# Sheet3_MCU.net
KiCad netlist of a schematic drawn in Altium Designer
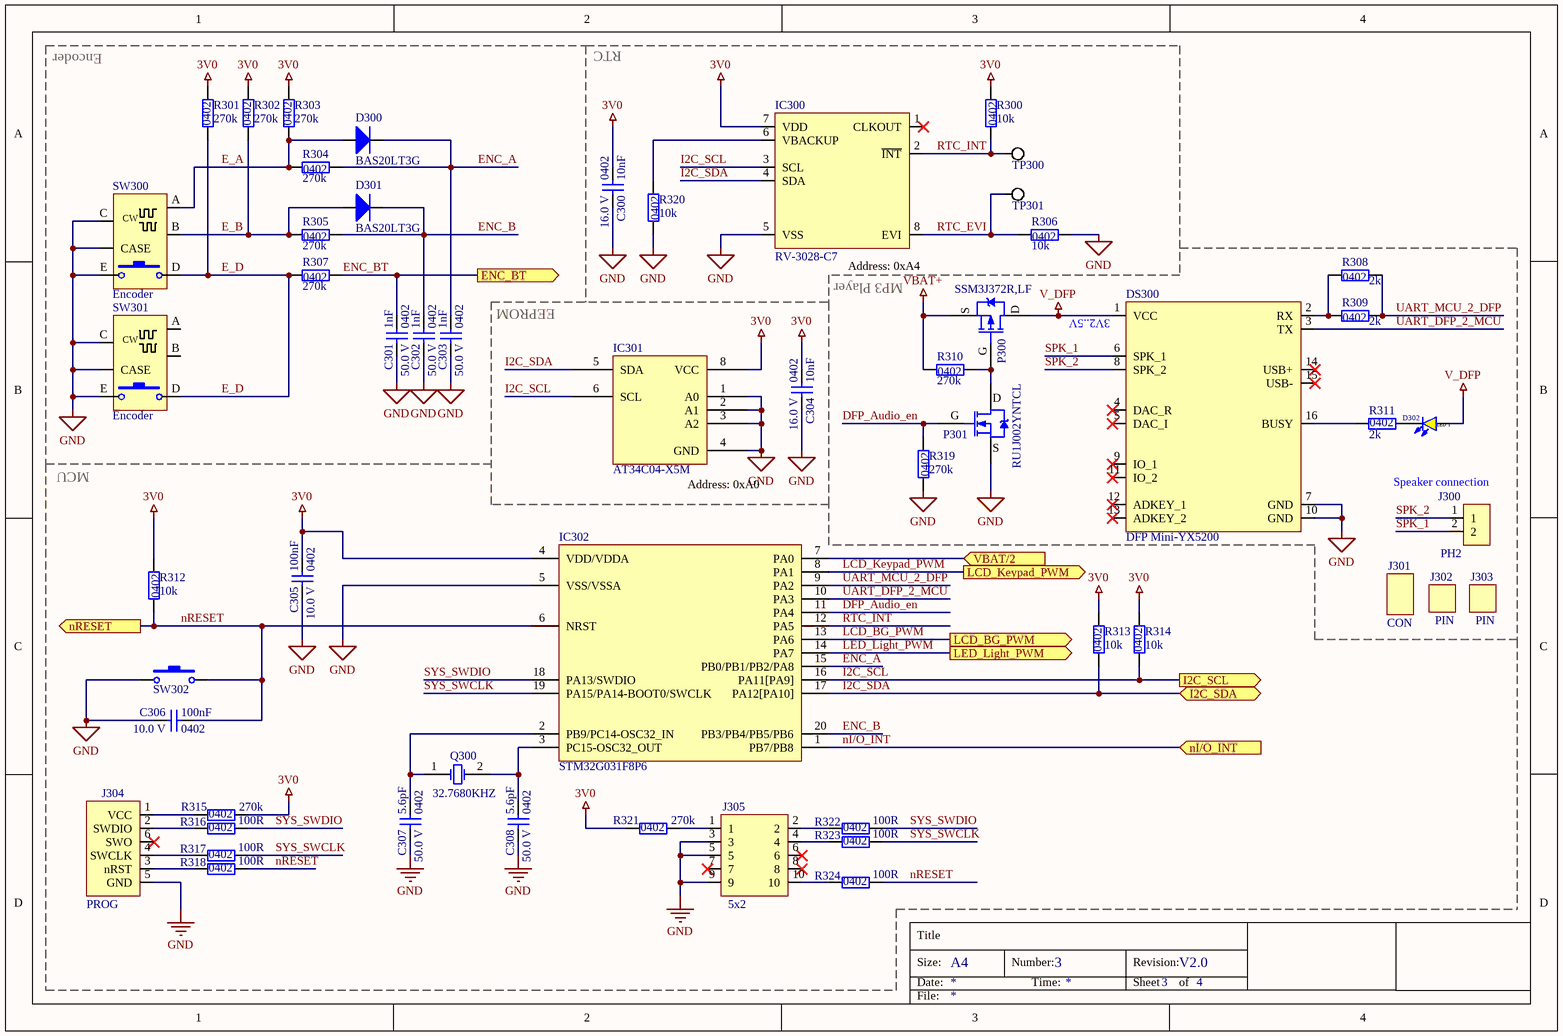
[diagram p0: Sheet3_MCU.SchDoc]

(export (version "E")
  (design (tool "Eeschema 10.0.6"))
  (components
    (comp (ref "C300")
      (value "C 10nF 0402 16V")
      (footprint "0402")
      (description "CAP CER 10000PF 16V Y5V 0402")
      (fields
        (field (name "MANUFACTURER") "Samsung Electro-Mechanics")
        (field (name "MANUFACTURER PART NUMBER") "CL05F103ZO5NNNC")
        (field (name "CAPACITANCE") "10nF")
        (field (name "VOLTAGE") "16.0 V")
      )
      (libsource (lib "CS_Part_Library") (part "CAP_10nF_16V_0402"))
    )
    (comp (ref "C301")
      (value "C 1nF 0402 50V")
      (footprint "0402")
      (description "CAP CER 1000PF 50V C0G/NP0 0402")
      (fields
        (field (name "MANUFACTURER") "Murata Electronics")
        (field (name "MANUFACTURER PART NUMBER") "GRM1555C1H102JA01J")
        (field (name "CAPACITANCE") "1nF")
        (field (name "VOLTAGE") "50.0 V")
      )
      (libsource (lib "CS_Part_Library") (part "CAP_1nF_50V_0402"))
    )
    (comp (ref "C302")
      (value "C 1nF 0402 50V")
      (footprint "0402")
      (description "CAP CER 1000PF 50V C0G/NP0 0402")
      (fields
        (field (name "MANUFACTURER") "Murata Electronics")
        (field (name "MANUFACTURER PART NUMBER") "GRM1555C1H102JA01J")
        (field (name "CAPACITANCE") "1nF")
        (field (name "VOLTAGE") "50.0 V")
      )
      (libsource (lib "CS_Part_Library") (part "CAP_1nF_50V_0402"))
    )
    (comp (ref "C303")
      (value "C 1nF 0402 50V")
      (footprint "0402")
      (description "CAP CER 1000PF 50V C0G/NP0 0402")
      (fields
        (field (name "MANUFACTURER") "Murata Electronics")
        (field (name "MANUFACTURER PART NUMBER") "GRM1555C1H102JA01J")
        (field (name "CAPACITANCE") "1nF")
        (field (name "VOLTAGE") "50.0 V")
      )
      (libsource (lib "CS_Part_Library") (part "CAP_1nF_50V_0402"))
    )
    (comp (ref "C304")
      (value "C 10nF 0402 16V")
      (footprint "0402")
      (description "CAP CER 10000PF 16V Y5V 0402")
      (fields
        (field (name "MANUFACTURER") "Samsung Electro-Mechanics")
        (field (name "MANUFACTURER PART NUMBER") "CL05F103ZO5NNNC")
        (field (name "CAPACITANCE") "10nF")
        (field (name "VOLTAGE") "16.0 V")
      )
      (libsource (lib "CS_Part_Library") (part "CAP_10nF_16V_0402"))
    )
    (comp (ref "C305")
      (value "C 100nF 0402 10V")
      (footprint "0402")
      (description "CAP CER 0.1UF 10V X5R 0402")
      (fields
        (field (name "MANUFACTURER") "Samsung Electro-Mechanics")
        (field (name "MANUFACTURER PART NUMBER") "CL05A104MP5NNNC")
        (field (name "CAPACITANCE") "100nF")
        (field (name "VOLTAGE") "10.0 V")
      )
      (libsource (lib "CS_Part_Library") (part "CAP_100nF_10V_0402"))
    )
    (comp (ref "C306")
      (value "C 100nF 0402 10V")
      (footprint "0402")
      (description "CAP CER 0.1UF 10V X5R 0402")
      (fields
        (field (name "MANUFACTURER") "Samsung Electro-Mechanics")
        (field (name "MANUFACTURER PART NUMBER") "CL05A104MP5NNNC")
        (field (name "CAPACITANCE") "100nF")
        (field (name "VOLTAGE") "10.0 V")
      )
      (libsource (lib "CS_Part_Library") (part "CAP_100nF_10V_0402"))
    )
    (comp (ref "C307")
      (value "C 5.6pF 0402 50V")
      (footprint "0402")
      (description "CAP CER 5.6PF 50V C0G/NP0 0402")
      (fields
        (field (name "MANUFACTURER") "Samsung Electro-Mechanics")
        (field (name "MANUFACTURER PART NUMBER") "CL05C5R6DB5NNNC")
        (field (name "CAPACITANCE") "5.6pF")
        (field (name "VOLTAGE") "50.0 V")
      )
      (libsource (lib "CS_Part_Library") (part "CAP_5.6PF_50V_0402"))
    )
    (comp (ref "C308")
      (value "C 5.6pF 0402 50V")
      (footprint "0402")
      (description "CAP CER 5.6PF 50V C0G/NP0 0402")
      (fields
        (field (name "MANUFACTURER") "Samsung Electro-Mechanics")
        (field (name "MANUFACTURER PART NUMBER") "CL05C5R6DB5NNNC")
        (field (name "CAPACITANCE") "5.6pF")
        (field (name "VOLTAGE") "50.0 V")
      )
      (libsource (lib "CS_Part_Library") (part "CAP_5.6PF_50V_0402"))
    )
    (comp (ref "D300")
      (value "BAS20LT3G")
      (footprint "SOT-23-3")
      (description "DIODE GP 200V 200MA SOT23-3")
      (fields (field (name "MANUFACTURER") "onsemi") (field (name "MANUFACTURER PART NUMBER") "BAS20LT3G"))
      (libsource (lib "Symbols") (part "D_LL_200V_200mA"))
    )
    (comp (ref "D301")
      (value "BAS20LT3G")
      (footprint "SOT-23-3")
      (description "DIODE GP 200V 200MA SOT23-3")
      (fields (field (name "MANUFACTURER") "onsemi") (field (name "MANUFACTURER PART NUMBER") "BAS20LT3G"))
      (libsource (lib "Symbols") (part "D_LL_200V_200mA"))
    )
    (comp (ref "D302")
      (value "LED Y")
      (footprint "LED_0603")
      (description "LED YELLOW DIFFUSED")
      (fields
        (field (name "MANUFACTURER") "Stanley Electric Co")
        (field (name "MANUFACTURER PART NUMBER") "FKY1111C-TR")
      )
      (libsource (lib "CS_Part_Library") (part "D_LED_Yellow_0603"))
    )
    (comp (ref "DS300")
      (value "DFP Mini-YX5200")
      (footprint "DFP_Player_Mini")
      (description "Mini-YX5200 Audio MP3 Modul")
      (fields (field (name "MANUFACTURER") "DFRobot") (field (name "MANUFACTURER PART NUMBER") "DFR0299"))
      (libsource (lib "CS_Part_Library") (part "DFP_Player_mini"))
    )
    (comp (ref "IC300")
      (value "RV-3028-C7")
      (footprint "MC-C7")
      (description "IC RTC CLK/CALENDAR I2C 10SON")
      (fields
        (field (name "MANUFACTURER") "Micro Crystal AG")
        (field (name "MANUFACTURER PART NUMBER") "RV-3028-C7TAQC")
      )
      (libsource (lib "Symbols") (part "IC_RTC_3028-C7"))
    )
    (comp (ref "IC301")
      (value "AT34C04-X5M")
      (footprint "TSSOP-8_4.4mm")
      (description "IC EEPROM 4KBIT I2C 1MHZ 8TSSOP")
      (fields
        (field (name "MANUFACTURER") "Microchip Technology")
        (field (name "MANUFACTURER PART NUMBER") "AT34C04-X5M-T")
      )
      (libsource (lib "CS_Part_Library") (part "IC_EEPROM_AT34C04"))
    )
    (comp (ref "IC302")
      (value "STM32G031F8P6")
      (footprint "TSSOP-20")
      (description "IC MCU 32BIT 32KB FLASH 20TSSOP")
      (fields (field (name "MANUFACTURER") "STMicroelectronics"))
      (libsource (lib "CS_Part_Library") (part "IC_MCU_STM32G031F8P6"))
    )
    (comp (ref "J300")
      (value "PH2")
      (footprint "J_S2B-PH-K-S")
      (description "CONN HEADER R/A 2POS 2MM")
      (fields
        (field (name "MANUFACTURER") "JST Sales America Inc.")
        (field (name "MANUFACTURER PART NUMBER") "S2B-PH-KL(LF)(SN)")
      )
      (libsource (lib "Symbols") (part "J_S2B-PH-KL"))
    )
    (comp (ref "J301")
      (value "CON")
      (description "CONN CONNECTOR PH 2POS 2MM")
      (fields
        (field (name "MANUFACTURER") "JST Sales America Inc.")
        (field (name "MANUFACTURER PART NUMBER") "PHR-2-R")
      )
      (libsource (lib "Symbols") (part "J_PHR-2-R"))
    )
    (comp (ref "J302")
      (value "PIN")
      (description "PIN INSERT")
      (fields
        (field (name "MANUFACTURER") "JST Sales America Inc.")
        (field (name "MANUFACTURER PART NUMBER") "SPH-004T-P0.5S")
      )
      (libsource (lib "Symbols") (part "J_PHR-2-R_PIN"))
    )
    (comp (ref "J303")
      (value "PIN")
      (description "PIN INSERT")
      (fields
        (field (name "MANUFACTURER") "JST Sales America Inc.")
        (field (name "MANUFACTURER PART NUMBER") "SPH-004T-P0.5S")
      )
      (libsource (lib "Symbols") (part "J_PHR-2-R_PIN"))
    )
    (comp (ref "J304")
      (value "PROG")
      (footprint "J_TC2030-IDC-NL")
      (description "SWD Programmer No Legs")
      (fields (field (name "MANUFACTURER") "Tag_connect") (field (name "MANUFACTURER PART NUMBER") "TC2030"))
      (libsource (lib "CS_Part_Library") (part "J_TC2030-IDC-NL"))
    )
    (comp (ref "J305")
      (value "5x2")
      (footprint "J_MH5x2_1.27-STM32")
      (description "CONN HEADER SMD 10POS 1.27MM")
      (fields
        (field (name "MANUFACTURER") "Sullins Connector Solutions")
        (field (name "MANUFACTURER PART NUMBER") "GRPB052VWQS-RC")
      )
      (libsource (lib "Symbols") (part "J_MH5x2_1.27"))
    )
    (comp (ref "P300")
      (value "P PMOS 30V 6A")
      (footprint "SOT-23-3-F")
      (description "MOSFET P-CH 30V 6A SOT23F")
      (fields
        (field (name "MANUFACTURER") "Toshiba Semiconductor and Storage")
        (field (name "MANUFACTURER PART NUMBER") "SSM3J372R,LF")
      )
      (libsource (lib "CS_Part_Library") (part "P_PCH_30V_1W"))
    )
    (comp (ref "P301")
      (value "P_NCH_50V_150mW")
      (footprint "UMT3F")
      (description "MOSFET N-CH 50V 200MA UMT3F")
      (fields
        (field (name "MANUFACTURER") "Rohm Semiconductor")
        (field (name "MANUFACTURER PART NUMBER") "RU1J002YNTCL")
      )
      (libsource (lib "CS_Part_Library") (part "P_NCH_50V_150mW"))
    )
    (comp (ref "Q300")
      (value "32.7680KHZ")
      (footprint "Q2_3.2x1.5")
      (description "CRYSTAL 32.7680KHZ 12.5PF SMD")
      (fields
        (field (name "MANUFACTURER") "NDK America, Inc.")
        (field (name "MANUFACTURER PART NUMBER") "NX3215SA-32.768K-EXS00A-MU00003")
      )
      (libsource (lib "CS_Part_Library") (part "Q_32k768_12p5"))
    )
    (comp (ref "R300")
      (value "R 10k 0402")
      (footprint "0402")
      (description "RES 10K OHM 1% 1/16W 0402")
      (fields
        (field (name "MANUFACTURER") "YAGEO")
        (field (name "MANUFACTURER PART NUMBER") "RC0402FR-0710KL")
        (field (name "RESISTANCE") "10k")
      )
      (libsource (lib "CS_Part_Library") (part "R_10k_0402"))
    )
    (comp (ref "R301")
      (value "R 270k 0402")
      (footprint "0402")
      (description "RES 270K OHM 1% 1/16W 0402")
      (fields
        (field (name "MANUFACTURER") "YAGEO")
        (field (name "MANUFACTURER PART NUMBER") "RC0402FR-07270KL")
        (field (name "RESISTANCE") "270k")
      )
      (libsource (lib "CS_Part_Library") (part "R_270k_0402"))
    )
    (comp (ref "R302")
      (value "R 270k 0402")
      (footprint "0402")
      (description "RES 270K OHM 1% 1/16W 0402")
      (fields
        (field (name "MANUFACTURER") "YAGEO")
        (field (name "MANUFACTURER PART NUMBER") "RC0402FR-07270KL")
        (field (name "RESISTANCE") "270k")
      )
      (libsource (lib "CS_Part_Library") (part "R_270k_0402"))
    )
    (comp (ref "R303")
      (value "R 270k 0402")
      (footprint "0402")
      (description "RES 270K OHM 1% 1/16W 0402")
      (fields
        (field (name "MANUFACTURER") "YAGEO")
        (field (name "MANUFACTURER PART NUMBER") "RC0402FR-07270KL")
        (field (name "RESISTANCE") "270k")
      )
      (libsource (lib "CS_Part_Library") (part "R_270k_0402"))
    )
    (comp (ref "R304")
      (value "R 270k 0402")
      (footprint "0402")
      (description "RES 270K OHM 1% 1/16W 0402")
      (fields
        (field (name "MANUFACTURER") "YAGEO")
        (field (name "MANUFACTURER PART NUMBER") "RC0402FR-07270KL")
        (field (name "RESISTANCE") "270k")
      )
      (libsource (lib "") (part "R_270k_0402_1"))
    )
    (comp (ref "R305")
      (value "R 270k 0402")
      (footprint "0402")
      (description "RES 270K OHM 1% 1/16W 0402")
      (fields
        (field (name "MANUFACTURER") "YAGEO")
        (field (name "MANUFACTURER PART NUMBER") "RC0402FR-07270KL")
        (field (name "RESISTANCE") "270k")
      )
      (libsource (lib "") (part "R_270k_0402_1"))
    )
    (comp (ref "R306")
      (value "R 10k 0402")
      (footprint "0402")
      (description "RES 10K OHM 1% 1/16W 0402")
      (fields
        (field (name "MANUFACTURER") "YAGEO")
        (field (name "MANUFACTURER PART NUMBER") "RC0402FR-0710KL")
        (field (name "RESISTANCE") "10k")
      )
      (libsource (lib "") (part "R_10k_0402_1"))
    )
    (comp (ref "R307")
      (value "R 270k 0402")
      (footprint "0402")
      (description "RES 270K OHM 1% 1/16W 0402")
      (fields
        (field (name "MANUFACTURER") "YAGEO")
        (field (name "MANUFACTURER PART NUMBER") "RC0402FR-07270KL")
        (field (name "RESISTANCE") "270k")
      )
      (libsource (lib "") (part "R_270k_0402_1"))
    )
    (comp (ref "R308")
      (value "R 2k 0402")
      (footprint "0402")
      (description "RES 2K OHM 1% 1/16W 0402")
      (fields
        (field (name "MANUFACTURER") "Stackpole Electronics Inc")
        (field (name "MANUFACTURER PART NUMBER") "RMCF0402FT2K00")
        (field (name "RESISTANCE") "2k")
      )
      (libsource (lib "CS_Part_Library") (part "R_2k_0402"))
    )
    (comp (ref "R309")
      (value "R 2k 0402")
      (footprint "0402")
      (description "RES 2K OHM 1% 1/16W 0402")
      (fields
        (field (name "MANUFACTURER") "Stackpole Electronics Inc")
        (field (name "MANUFACTURER PART NUMBER") "RMCF0402FT2K00")
        (field (name "RESISTANCE") "2k")
      )
      (libsource (lib "CS_Part_Library") (part "R_2k_0402"))
    )
    (comp (ref "R310")
      (value "R 270k 0402")
      (footprint "0402")
      (description "RES 270K OHM 1% 1/16W 0402")
      (fields
        (field (name "MANUFACTURER") "YAGEO")
        (field (name "MANUFACTURER PART NUMBER") "RC0402FR-07270KL")
        (field (name "RESISTANCE") "270k")
      )
      (libsource (lib "") (part "R_270k_0402_1"))
    )
    (comp (ref "R311")
      (value "R 2k 0402")
      (footprint "0402")
      (description "RES 2K OHM 1% 1/16W 0402")
      (fields
        (field (name "MANUFACTURER") "Stackpole Electronics Inc")
        (field (name "MANUFACTURER PART NUMBER") "RMCF0402FT2K00")
        (field (name "RESISTANCE") "2k")
      )
      (libsource (lib "") (part "R_2k_0402_1"))
    )
    (comp (ref "R312")
      (value "R 10k 0402")
      (footprint "0402")
      (description "RES 10K OHM 1% 1/16W 0402")
      (fields
        (field (name "MANUFACTURER") "YAGEO")
        (field (name "MANUFACTURER PART NUMBER") "RC0402FR-0710KL")
        (field (name "RESISTANCE") "10k")
      )
      (libsource (lib "CS_Part_Library") (part "R_10k_0402"))
    )
    (comp (ref "R313")
      (value "R 10k 0402")
      (footprint "0402")
      (description "RES 10K OHM 1% 1/16W 0402")
      (fields
        (field (name "MANUFACTURER") "YAGEO")
        (field (name "MANUFACTURER PART NUMBER") "RC0402FR-0710KL")
        (field (name "RESISTANCE") "10k")
      )
      (libsource (lib "") (part "R_10k_0402_1"))
    )
    (comp (ref "R314")
      (value "R 10k 0402")
      (footprint "0402")
      (description "RES 10K OHM 1% 1/16W 0402")
      (fields
        (field (name "MANUFACTURER") "YAGEO")
        (field (name "MANUFACTURER PART NUMBER") "RC0402FR-0710KL")
        (field (name "RESISTANCE") "10k")
      )
      (libsource (lib "") (part "R_10k_0402_1"))
    )
    (comp (ref "R315")
      (value "R 270k 0402")
      (footprint "0402")
      (description "RES 270K OHM 1% 1/16W 0402")
      (fields
        (field (name "MANUFACTURER") "YAGEO")
        (field (name "MANUFACTURER PART NUMBER") "RC0402FR-07270KL")
        (field (name "RESISTANCE") "270k")
      )
      (libsource (lib "") (part "R_270k_0402_3"))
    )
    (comp (ref "R316")
      (value "R 100R 0402")
      (footprint "0402")
      (description "RES 100 OHM 1% 1/16W 0402")
      (fields
        (field (name "MANUFACTURER") "Stackpole Electronics Inc")
        (field (name "MANUFACTURER PART NUMBER") "RMCF0402FT100R")
        (field (name "RESISTANCE") "100R")
      )
      (libsource (lib "Symbols") (part "R_100R_0402"))
    )
    (comp (ref "R317")
      (value "R 100R 0402")
      (footprint "0402")
      (description "RES 100 OHM 1% 1/16W 0402")
      (fields
        (field (name "MANUFACTURER") "Stackpole Electronics Inc")
        (field (name "MANUFACTURER PART NUMBER") "RMCF0402FT100R")
        (field (name "RESISTANCE") "100R")
      )
      (libsource (lib "Symbols") (part "R_100R_0402"))
    )
    (comp (ref "R318")
      (value "R 100R 0402")
      (footprint "0402")
      (description "RES 100 OHM 1% 1/16W 0402")
      (fields
        (field (name "MANUFACTURER") "Stackpole Electronics Inc")
        (field (name "MANUFACTURER PART NUMBER") "RMCF0402FT100R")
        (field (name "RESISTANCE") "100R")
      )
      (libsource (lib "Symbols") (part "R_100R_0402"))
    )
    (comp (ref "R319")
      (value "R 270k 0402")
      (footprint "0402")
      (description "RES 270K OHM 1% 1/16W 0402")
      (fields
        (field (name "MANUFACTURER") "YAGEO")
        (field (name "MANUFACTURER PART NUMBER") "RC0402FR-07270KL")
        (field (name "RESISTANCE") "270k")
      )
      (libsource (lib "") (part "R_270k_0402_2"))
    )
    (comp (ref "R320")
      (value "R 10k 0402")
      (footprint "0402")
      (description "RES 10K OHM 1% 1/16W 0402")
      (fields
        (field (name "MANUFACTURER") "YAGEO")
        (field (name "MANUFACTURER PART NUMBER") "RC0402FR-0710KL")
        (field (name "RESISTANCE") "10k")
      )
      (libsource (lib "CS_Part_Library") (part "R_10k_0402"))
    )
    (comp (ref "R321")
      (value "R 270k 0402")
      (footprint "0402")
      (description "RES 270K OHM 1% 1/16W 0402")
      (fields
        (field (name "MANUFACTURER") "YAGEO")
        (field (name "MANUFACTURER PART NUMBER") "RC0402FR-07270KL")
        (field (name "RESISTANCE") "270k")
      )
      (libsource (lib "") (part "R_270k_0402_3"))
    )
    (comp (ref "R322")
      (value "R 100R 0402")
      (footprint "0402")
      (description "RES 100 OHM 1% 1/16W 0402")
      (fields
        (field (name "MANUFACTURER") "Stackpole Electronics Inc")
        (field (name "MANUFACTURER PART NUMBER") "RMCF0402FT100R")
        (field (name "RESISTANCE") "100R")
      )
      (libsource (lib "Symbols") (part "R_100R_0402"))
    )
    (comp (ref "R323")
      (value "R 100R 0402")
      (footprint "0402")
      (description "RES 100 OHM 1% 1/16W 0402")
      (fields
        (field (name "MANUFACTURER") "Stackpole Electronics Inc")
        (field (name "MANUFACTURER PART NUMBER") "RMCF0402FT100R")
        (field (name "RESISTANCE") "100R")
      )
      (libsource (lib "Symbols") (part "R_100R_0402"))
    )
    (comp (ref "R324")
      (value "R 100R 0402")
      (footprint "0402")
      (description "RES 100 OHM 1% 1/16W 0402")
      (fields
        (field (name "MANUFACTURER") "Stackpole Electronics Inc")
        (field (name "MANUFACTURER PART NUMBER") "RMCF0402FT100R")
        (field (name "RESISTANCE") "100R")
      )
      (libsource (lib "Symbols") (part "R_100R_0402"))
    )
    (comp (ref "SW300")
      (value "Encoder")
      (footprint "PEC11R")
      (description "ROTARY ENCODER MECHANICAL 12PPR")
      (fields
        (field (name "MANUFACTURER") "Bourns Inc.")
        (field (name "MANUFACTURER PART NUMBER") "PEC11R-4220F-S0012")
      )
      (libsource (lib "CS_Part_Library") (part "ENC_12_THT"))
    )
    (comp (ref "SW301")
      (value "Encoder")
      (footprint "PEC11R")
      (description "ROTARY ENCODER MECHANICAL 12PPR")
      (fields
        (field (name "MANUFACTURER") "Bourns Inc.")
        (field (name "MANUFACTURER PART NUMBER") "PEC11R-4220F-S0012")
      )
      (libsource (lib "CS_Part_Library") (part "ENC_12_THT"))
    )
    (comp (ref "SW302")
      (value "SW")
      (footprint "SW_PTS810")
      (description "SWITCH TACTILE SPST-NO 0.05A 16V")
      (fields
        (field (name "MANUFACTURER") "C&K")
        (field (name "MANUFACTURER PART NUMBER") "PTS810 SJM 250 SMTR LFS")
      )
      (libsource (lib "Symbols") (part "SW_TactileSW_V"))
    )
    (comp (ref "TP300")
      (value "TP")
      (footprint "TP_1mm")
      (description "Test Point 1mm")
      (libsource (lib "CS_Part_Library") (part "TP_1mm"))
    )
    (comp (ref "TP301")
      (value "TP")
      (footprint "TP_1mm")
      (description "Test Point 1mm")
      (libsource (lib "CS_Part_Library") (part "TP_1mm"))
    )
  )
  (nets
    (net (code "1") (name "/DFP_Audio_en") (class "Default")
      (node (ref "IC302") (pin "11") (pinfunction "PA4_11") (pintype "passive"))
      (node (ref "P301") (pin "1") (pinfunction "G_1") (pintype "passive"))
      (node (ref "R319") (pin "1") (pinfunction "1_1") (pintype "passive"))
    )
    (net (code "2") (name "/ENC_A") (class "Default")
      (node (ref "C303") (pin "2") (pinfunction "2_2") (pintype "passive"))
      (node (ref "D300") (pin "3") (pinfunction "K_3") (pintype "passive"))
      (node (ref "IC302") (pin "15") (pinfunction "PB0/PB1/PB2/PA8_15") (pintype "passive"))
      (node (ref "R304") (pin "1") (pinfunction "1_1") (pintype "passive"))
    )
    (net (code "3") (name "/ENC_B") (class "Default")
      (node (ref "C302") (pin "2") (pinfunction "2_2") (pintype "passive"))
      (node (ref "D301") (pin "3") (pinfunction "K_3") (pintype "passive"))
      (node (ref "IC302") (pin "20") (pinfunction "PB3/PB4/PB5/PB6_20") (pintype "passive"))
      (node (ref "R305") (pin "1") (pinfunction "1_1") (pintype "passive"))
    )
    (net (code "4") (name "/ENC_BT") (class "Default")
      (node (ref "C301") (pin "2") (pinfunction "2_2") (pintype "passive"))
      (node (ref "R307") (pin "1") (pinfunction "1_1") (pintype "passive"))
    )
    (net (code "5") (name "/E_A") (class "Default")
      (node (ref "D300") (pin "1") (pinfunction "A_1") (pintype "passive"))
      (node (ref "R303") (pin "1") (pinfunction "1_1") (pintype "passive"))
      (node (ref "R304") (pin "2") (pinfunction "2_2") (pintype "passive"))
      (node (ref "SW300") (pin "A") (pinfunction "A_A") (pintype "passive"))
    )
    (net (code "6") (name "/E_B") (class "Default")
      (node (ref "D301") (pin "1") (pinfunction "A_1") (pintype "passive"))
      (node (ref "R302") (pin "1") (pinfunction "1_1") (pintype "passive"))
      (node (ref "R305") (pin "2") (pinfunction "2_2") (pintype "passive"))
      (node (ref "SW300") (pin "B") (pinfunction "B_B") (pintype "passive"))
    )
    (net (code "7") (name "/E_D") (class "Default")
      (node (ref "R301") (pin "1") (pinfunction "1_1") (pintype "passive"))
      (node (ref "R307") (pin "2") (pinfunction "2_2") (pintype "passive"))
      (node (ref "SW300") (pin "D") (pinfunction "D_D") (pintype "passive"))
      (node (ref "SW301") (pin "D") (pinfunction "D_D") (pintype "passive"))
    )
    (net (code "8") (name "/I2C_SCL") (class "Default")
      (node (ref "IC300") (pin "3") (pinfunction "SCL_3") (pintype "passive"))
      (node (ref "IC301") (pin "6") (pinfunction "SCL_6") (pintype "passive"))
      (node (ref "IC302") (pin "16") (pinfunction "PA11[PA9]_16") (pintype "passive"))
      (node (ref "R314") (pin "1") (pinfunction "1_1") (pintype "passive"))
    )
    (net (code "9") (name "/I2C_SDA") (class "Default")
      (node (ref "IC300") (pin "4") (pinfunction "SDA_4") (pintype "passive"))
      (node (ref "IC301") (pin "5") (pinfunction "SDA_5") (pintype "passive"))
      (node (ref "IC302") (pin "17") (pinfunction "PA12[PA10]_17") (pintype "passive"))
      (node (ref "R313") (pin "1") (pinfunction "1_1") (pintype "passive"))
    )
    (net (code "10") (name "/LCD_BG_PWM") (class "Default")
      (node (ref "IC302") (pin "13") (pinfunction "PA6_13") (pintype "passive"))
    )
    (net (code "11") (name "/LCD_Keypad_PWM") (class "Default")
      (node (ref "IC302") (pin "8") (pinfunction "PA1_8") (pintype "passive"))
    )
    (net (code "12") (name "/LED_Light_PWM") (class "Default")
      (node (ref "IC302") (pin "14") (pinfunction "PA7_14") (pintype "passive"))
    )
    (net (code "13") (name "/RTC_EVI") (class "Default")
      (node (ref "IC300") (pin "8") (pinfunction "EVI_8") (pintype "passive"))
      (node (ref "R306") (pin "1") (pinfunction "1_1") (pintype "passive"))
      (node (ref "TP301") (pin "1") (pinfunction "TP_1") (pintype "passive"))
    )
    (net (code "14") (name "/RTC_INT") (class "Default")
      (node (ref "IC300") (pin "2") (pinfunction "~{INT}_2") (pintype "passive"))
      (node (ref "IC302") (pin "12") (pinfunction "PA5_12") (pintype "passive"))
      (node (ref "R300") (pin "1") (pinfunction "1_1") (pintype "passive"))
      (node (ref "TP300") (pin "1") (pinfunction "TP_1") (pintype "passive"))
    )
    (net (code "15") (name "/SPK_1") (class "Default")
      (node (ref "DS300") (pin "6") (pinfunction "SPK_1_6") (pintype "passive"))
      (node (ref "J300") (pin "2") (pinfunction "2_2") (pintype "passive"))
    )
    (net (code "16") (name "/SPK_2") (class "Default")
      (node (ref "DS300") (pin "8") (pinfunction "SPK_2_8") (pintype "passive"))
      (node (ref "J300") (pin "1") (pinfunction "1_1") (pintype "passive"))
    )
    (net (code "17") (name "/SYS_SWCLK") (class "Default")
      (node (ref "IC302") (pin "19") (pinfunction "PA15/PA14-BOOT0/SWCLK_19") (pintype "passive"))
      (node (ref "R317") (pin "2") (pinfunction "2_2") (pintype "passive"))
      (node (ref "R323") (pin "2") (pinfunction "2_2") (pintype "passive"))
    )
    (net (code "18") (name "/SYS_SWDIO") (class "Default")
      (node (ref "IC302") (pin "18") (pinfunction "PA13/SWDIO_18") (pintype "passive"))
      (node (ref "R316") (pin "2") (pinfunction "2_2") (pintype "passive"))
      (node (ref "R322") (pin "2") (pinfunction "2_2") (pintype "passive"))
    )
    (net (code "19") (name "/UART_DFP_2_MCU") (class "Default")
      (node (ref "DS300") (pin "3") (pinfunction "TX_3") (pintype "passive"))
      (node (ref "IC302") (pin "10") (pinfunction "PA3_10") (pintype "passive"))
    )
    (net (code "20") (name "/UART_MCU_2_DFP") (class "Default")
      (node (ref "IC302") (pin "9") (pinfunction "PA2_9") (pintype "passive"))
      (node (ref "R308") (pin "1") (pinfunction "1_1") (pintype "passive"))
      (node (ref "R309") (pin "1") (pinfunction "1_1") (pintype "passive"))
    )
    (net (code "21") (name "/VBAT{slash}2") (class "Default")
      (node (ref "IC302") (pin "7") (pinfunction "PA0_7") (pintype "passive"))
    )
    (net (code "22") (name "/nI{slash}O_INT") (class "Default")
      (node (ref "IC302") (pin "1") (pinfunction "PB7/PB8_1") (pintype "passive"))
    )
    (net (code "23") (name "/nRESET") (class "Default")
      (node (ref "C306") (pin "2") (pinfunction "2_2") (pintype "passive"))
      (node (ref "IC302") (pin "6") (pinfunction "NRST_6") (pintype "passive"))
      (node (ref "R312") (pin "1") (pinfunction "1_1") (pintype "passive"))
      (node (ref "R318") (pin "2") (pinfunction "2_2") (pintype "passive"))
      (node (ref "R324") (pin "2") (pinfunction "2_2") (pintype "passive"))
      (node (ref "SW302") (pin "3") (pinfunction "2,_3_3") (pintype "passive"))
    )
    (net (code "24") (name "3V0") (class "Default")
      (node (ref "C300") (pin "2") (pinfunction "2_2") (pintype "passive"))
      (node (ref "C304") (pin "2") (pinfunction "2_2") (pintype "passive"))
      (node (ref "C305") (pin "2") (pinfunction "2_2") (pintype "passive"))
      (node (ref "IC300") (pin "7") (pinfunction "VDD_7") (pintype "passive"))
      (node (ref "IC301") (pin "8") (pinfunction "VCC_8") (pintype "passive"))
      (node (ref "IC302") (pin "4") (pinfunction "VDD/VDDA_4") (pintype "passive"))
      (node (ref "R300") (pin "2") (pinfunction "2_2") (pintype "passive"))
      (node (ref "R301") (pin "2") (pinfunction "2_2") (pintype "passive"))
      (node (ref "R302") (pin "2") (pinfunction "2_2") (pintype "passive"))
      (node (ref "R303") (pin "2") (pinfunction "2_2") (pintype "passive"))
      (node (ref "R312") (pin "2") (pinfunction "2_2") (pintype "passive"))
      (node (ref "R313") (pin "2") (pinfunction "2_2") (pintype "passive"))
      (node (ref "R314") (pin "2") (pinfunction "2_2") (pintype "passive"))
      (node (ref "R315") (pin "2") (pinfunction "2_2") (pintype "passive"))
      (node (ref "R321") (pin "1") (pinfunction "1_1") (pintype "passive"))
    )
    (net (code "25") (name "GND") (class "Default")
      (node (ref "C300") (pin "1") (pinfunction "1_1") (pintype "passive"))
      (node (ref "C301") (pin "1") (pinfunction "1_1") (pintype "passive"))
      (node (ref "C302") (pin "1") (pinfunction "1_1") (pintype "passive"))
      (node (ref "C303") (pin "1") (pinfunction "1_1") (pintype "passive"))
      (node (ref "C304") (pin "1") (pinfunction "1_1") (pintype "passive"))
      (node (ref "C305") (pin "1") (pinfunction "1_1") (pintype "passive"))
      (node (ref "C306") (pin "1") (pinfunction "1_1") (pintype "passive"))
      (node (ref "C307") (pin "1") (pinfunction "1_1") (pintype "passive"))
      (node (ref "C308") (pin "1") (pinfunction "1_1") (pintype "passive"))
      (node (ref "DS300") (pin "10") (pinfunction "GND_10") (pintype "passive"))
      (node (ref "DS300") (pin "7") (pinfunction "GND_7") (pintype "passive"))
      (node (ref "IC300") (pin "5") (pinfunction "VSS_5") (pintype "passive"))
      (node (ref "IC301") (pin "1") (pinfunction "A0_1") (pintype "passive"))
      (node (ref "IC301") (pin "2") (pinfunction "A1_2") (pintype "passive"))
      (node (ref "IC301") (pin "3") (pinfunction "A2_3") (pintype "passive"))
      (node (ref "IC301") (pin "4") (pinfunction "GND_4") (pintype "passive"))
      (node (ref "IC302") (pin "5") (pinfunction "VSS/VSSA_5") (pintype "passive"))
      (node (ref "J304") (pin "5") (pinfunction "GND_5") (pintype "passive"))
      (node (ref "J305") (pin "3") (pinfunction "3_3") (pintype "passive"))
      (node (ref "J305") (pin "5") (pinfunction "5_5") (pintype "passive"))
      (node (ref "J305") (pin "9") (pinfunction "9_9") (pintype "passive"))
      (node (ref "P301") (pin "2") (pinfunction "S_2") (pintype "passive"))
      (node (ref "R306") (pin "2") (pinfunction "2_2") (pintype "passive"))
      (node (ref "R319") (pin "2") (pinfunction "2_2") (pintype "passive"))
      (node (ref "R320") (pin "1") (pinfunction "1_1") (pintype "passive"))
      (node (ref "SW300") (pin "C") (pinfunction "C_C") (pintype "passive"))
      (node (ref "SW300") (pin "CASE") (pinfunction "CASE_CASE") (pintype "passive"))
      (node (ref "SW300") (pin "E") (pinfunction "E_E") (pintype "passive"))
      (node (ref "SW301") (pin "C") (pinfunction "C_C") (pintype "passive"))
      (node (ref "SW301") (pin "CASE") (pinfunction "CASE_CASE") (pintype "passive"))
      (node (ref "SW301") (pin "E") (pinfunction "E_E") (pintype "passive"))
      (node (ref "SW302") (pin "1") (pinfunction "1,_2_1") (pintype "passive"))
    )
    (net (code "26") (name "Net-(D302-PadK)") (class "Default")
      (node (ref "D302") (pin "K") (pinfunction "K_K") (pintype "passive"))
      (node (ref "R311") (pin "2") (pinfunction "2_2") (pintype "passive"))
    )
    (net (code "27") (name "Net-(DS300-BUSY)") (class "Default")
      (node (ref "DS300") (pin "16") (pinfunction "BUSY_16") (pintype "passive"))
      (node (ref "R311") (pin "1") (pinfunction "1_1") (pintype "passive"))
    )
    (net (code "28") (name "Net-(DS300-RX)") (class "Default")
      (node (ref "DS300") (pin "2") (pinfunction "RX_2") (pintype "passive"))
      (node (ref "R308") (pin "2") (pinfunction "2_2") (pintype "passive"))
      (node (ref "R309") (pin "2") (pinfunction "2_2") (pintype "passive"))
    )
    (net (code "29") (name "Net-(IC300-VBACKUP)") (class "Default")
      (node (ref "IC300") (pin "6") (pinfunction "VBACKUP_6") (pintype "passive"))
      (node (ref "R320") (pin "2") (pinfunction "2_2") (pintype "passive"))
    )
    (net (code "30") (name "Net-(IC302-PB9{slash}PC14-OSC32_IN)") (class "Default")
      (node (ref "C307") (pin "2") (pinfunction "2_2") (pintype "passive"))
      (node (ref "IC302") (pin "2") (pinfunction "PB9/PC14-OSC32_IN_2") (pintype "passive"))
      (node (ref "Q300") (pin "1") (pinfunction "OSC1_1") (pintype "passive"))
    )
    (net (code "31") (name "Net-(IC302-PC15-OSC32_OUT)") (class "Default")
      (node (ref "C308") (pin "2") (pinfunction "2_2") (pintype "passive"))
      (node (ref "IC302") (pin "3") (pinfunction "PC15-OSC32_OUT_3") (pintype "passive"))
      (node (ref "Q300") (pin "2") (pinfunction "OSC2_2") (pintype "passive"))
    )
    (net (code "32") (name "Net-(J304-SWCLK)") (class "Default")
      (node (ref "J304") (pin "4") (pinfunction "SWCLK_4") (pintype "passive"))
      (node (ref "R317") (pin "1") (pinfunction "1_1") (pintype "passive"))
    )
    (net (code "33") (name "Net-(J304-SWDIO)") (class "Default")
      (node (ref "J304") (pin "2") (pinfunction "SWDIO_2") (pintype "passive"))
      (node (ref "R316") (pin "1") (pinfunction "1_1") (pintype "passive"))
    )
    (net (code "34") (name "Net-(J304-VCC)") (class "Default")
      (node (ref "J304") (pin "1") (pinfunction "VCC_1") (pintype "passive"))
      (node (ref "R315") (pin "1") (pinfunction "1_1") (pintype "passive"))
    )
    (net (code "35") (name "Net-(J304-nRST)") (class "Default")
      (node (ref "J304") (pin "3") (pinfunction "nRST_3") (pintype "passive"))
      (node (ref "R318") (pin "1") (pinfunction "1_1") (pintype "passive"))
    )
    (net (code "36") (name "Net-(J305-Pad1)") (class "Default")
      (node (ref "J305") (pin "1") (pinfunction "1_1") (pintype "passive"))
      (node (ref "R321") (pin "2") (pinfunction "2_2") (pintype "passive"))
    )
    (net (code "37") (name "Net-(J305-Pad2)") (class "Default")
      (node (ref "J305") (pin "2") (pinfunction "2_2") (pintype "passive"))
      (node (ref "R322") (pin "1") (pinfunction "1_1") (pintype "passive"))
    )
    (net (code "38") (name "Net-(J305-Pad4)") (class "Default")
      (node (ref "J305") (pin "4") (pinfunction "4_4") (pintype "passive"))
      (node (ref "R323") (pin "1") (pinfunction "1_1") (pintype "passive"))
    )
    (net (code "39") (name "Net-(J305-Pad10)") (class "Default")
      (node (ref "J305") (pin "10") (pinfunction "10_10") (pintype "passive"))
      (node (ref "R324") (pin "1") (pinfunction "1_1") (pintype "passive"))
    )
    (net (code "40") (name "Net-(P300-G)") (class "Default")
      (node (ref "P300") (pin "1") (pinfunction "G_1") (pintype "passive"))
      (node (ref "P301") (pin "3") (pinfunction "D_3") (pintype "passive"))
      (node (ref "R310") (pin "1") (pinfunction "1_1") (pintype "passive"))
    )
    (net (code "41") (name "VBAT+") (class "Default")
      (node (ref "P300") (pin "2") (pinfunction "S_2") (pintype "passive"))
      (node (ref "R310") (pin "2") (pinfunction "2_2") (pintype "passive"))
    )
    (net (code "42") (name "V_DFP") (class "Default")
      (node (ref "D302") (pin "A") (pinfunction "A_A") (pintype "passive"))
      (node (ref "DS300") (pin "1") (pinfunction "VCC_1") (pintype "passive"))
      (node (ref "P300") (pin "3") (pinfunction "D_3") (pintype "passive"))
    )
    (net (code "43") (name "unconnected-(DS300-ADKEY_1-Pad12)") (class "Default")
      (node (ref "DS300") (pin "12") (pinfunction "ADKEY_1_12") (pintype "passive+no_connect"))
    )
    (net (code "44") (name "unconnected-(DS300-ADKEY_2-Pad13)") (class "Default")
      (node (ref "DS300") (pin "13") (pinfunction "ADKEY_2_13") (pintype "passive+no_connect"))
    )
    (net (code "45") (name "unconnected-(DS300-DAC_I-Pad5)") (class "Default")
      (node (ref "DS300") (pin "5") (pinfunction "DAC_I_5") (pintype "passive+no_connect"))
    )
    (net (code "46") (name "unconnected-(DS300-DAC_R-Pad4)") (class "Default")
      (node (ref "DS300") (pin "4") (pinfunction "DAC_R_4") (pintype "passive+no_connect"))
    )
    (net (code "47") (name "unconnected-(DS300-IO_1-Pad9)") (class "Default")
      (node (ref "DS300") (pin "9") (pinfunction "IO_1_9") (pintype "passive+no_connect"))
    )
    (net (code "48") (name "unconnected-(DS300-IO_2-Pad11)") (class "Default")
      (node (ref "DS300") (pin "11") (pinfunction "IO_2_11") (pintype "passive+no_connect"))
    )
    (net (code "49") (name "unconnected-(DS300-USB+-Pad14)") (class "Default")
      (node (ref "DS300") (pin "14") (pinfunction "USB+_14") (pintype "passive+no_connect"))
    )
    (net (code "50") (name "unconnected-(DS300-USB--Pad15)") (class "Default")
      (node (ref "DS300") (pin "15") (pinfunction "USB-_15") (pintype "passive+no_connect"))
    )
    (net (code "51") (name "unconnected-(IC300-CLKOUT-Pad1)") (class "Default")
      (node (ref "IC300") (pin "1") (pinfunction "CLKOUT_1") (pintype "passive+no_connect"))
    )
    (net (code "52") (name "unconnected-(J304-SWO-Pad6)") (class "Default")
      (node (ref "J304") (pin "6") (pinfunction "SWO_6") (pintype "passive+no_connect"))
    )
    (net (code "53") (name "unconnected-(J305-Pad6)") (class "Default")
      (node (ref "J305") (pin "6") (pinfunction "6_6") (pintype "passive+no_connect"))
    )
    (net (code "54") (name "unconnected-(J305-Pad7)") (class "Default")
      (node (ref "J305") (pin "7") (pinfunction "7_7") (pintype "passive+no_connect"))
    )
    (net (code "55") (name "unconnected-(J305-Pad8)") (class "Default")
      (node (ref "J305") (pin "8") (pinfunction "8_8") (pintype "passive+no_connect"))
    )
    (net (code "56") (name "unconnected-(SW301-PadA)") (class "Default")
      (node (ref "SW301") (pin "A") (pinfunction "A_A") (pintype "passive"))
    )
    (net (code "57") (name "unconnected-(SW301-PadB)") (class "Default")
      (node (ref "SW301") (pin "B") (pinfunction "B_B") (pintype "passive"))
    )
  )
)
